# tmod-base.net
KiCad netlist of a schematic drawn in EAGLE
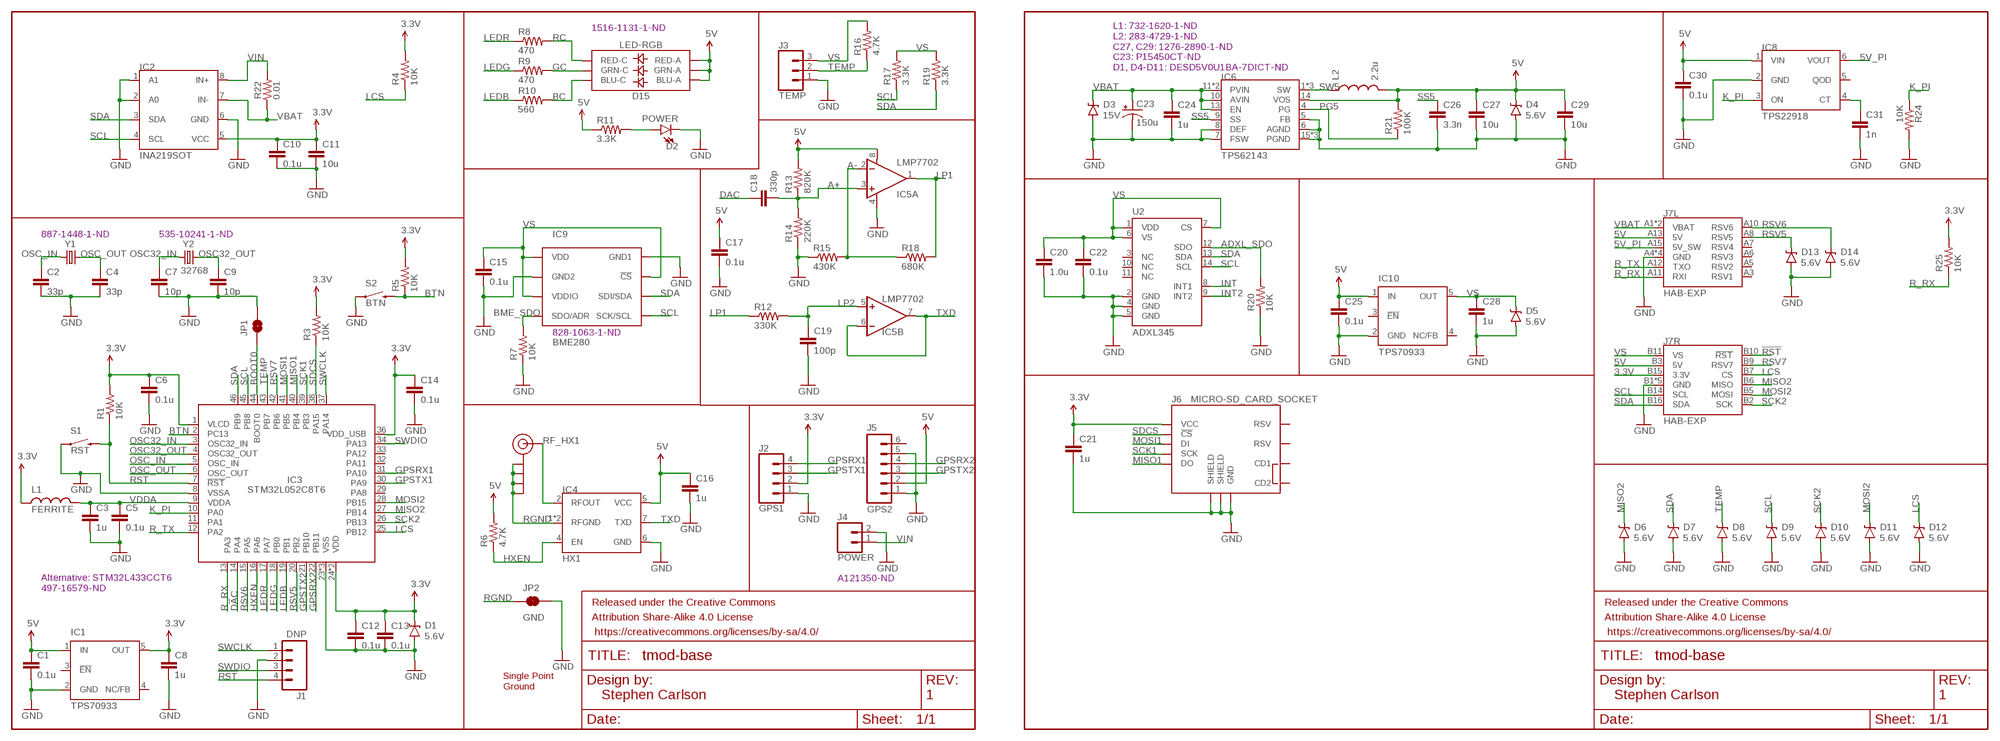
[diagram p0: schematic, sheet 1]

(export (version "E")
  (design (tool "Eeschema 10.0.6"))
  (components
    (comp (ref "C1")
      (value "0.1u")
      (footprint "eagle-import:0805")
      (libsource (lib "eagle-import") (part "CAP0805"))
    )
    (comp (ref "C2")
      (value "33p")
      (footprint "eagle-import:0805")
      (libsource (lib "eagle-import") (part "CAP0805"))
    )
    (comp (ref "C3")
      (value "1u")
      (footprint "eagle-import:0805")
      (libsource (lib "eagle-import") (part "CAP0805"))
    )
    (comp (ref "C4")
      (value "33p")
      (footprint "eagle-import:0805")
      (libsource (lib "eagle-import") (part "CAP0805"))
    )
    (comp (ref "C5")
      (value "0.1u")
      (footprint "eagle-import:0805")
      (libsource (lib "eagle-import") (part "CAP0805"))
    )
    (comp (ref "C6")
      (value "0.1u")
      (footprint "eagle-import:0805")
      (libsource (lib "eagle-import") (part "CAP0805"))
    )
    (comp (ref "C7")
      (value "10p")
      (footprint "eagle-import:0805")
      (libsource (lib "eagle-import") (part "CAP0805"))
    )
    (comp (ref "C8")
      (value "1u")
      (footprint "eagle-import:0805")
      (libsource (lib "eagle-import") (part "CAP0805"))
    )
    (comp (ref "C9")
      (value "10p")
      (footprint "eagle-import:0805")
      (libsource (lib "eagle-import") (part "CAP0805"))
    )
    (comp (ref "C10")
      (value "0.1u")
      (footprint "eagle-import:0805")
      (libsource (lib "eagle-import") (part "CAP0805"))
    )
    (comp (ref "C11")
      (value "10u")
      (footprint "eagle-import:0805")
      (libsource (lib "eagle-import") (part "CAP0805"))
    )
    (comp (ref "C12")
      (value "0.1u")
      (footprint "eagle-import:0805")
      (libsource (lib "eagle-import") (part "CAP0805"))
    )
    (comp (ref "C13")
      (value "0.1u")
      (footprint "eagle-import:0805")
      (libsource (lib "eagle-import") (part "CAP0805"))
    )
    (comp (ref "C14")
      (value "0.1u")
      (footprint "eagle-import:0805")
      (libsource (lib "eagle-import") (part "CAP0805"))
    )
    (comp (ref "C15")
      (value "0.1u")
      (footprint "eagle-import:0805")
      (libsource (lib "eagle-import") (part "CAP0805"))
    )
    (comp (ref "C16")
      (value "1u")
      (footprint "eagle-import:0805")
      (libsource (lib "eagle-import") (part "CAP0805"))
    )
    (comp (ref "C17")
      (value "0.1u")
      (footprint "eagle-import:0805")
      (libsource (lib "eagle-import") (part "CAP0805"))
    )
    (comp (ref "C18")
      (value "330p")
      (footprint "eagle-import:0805")
      (libsource (lib "eagle-import") (part "CAP0805"))
    )
    (comp (ref "C19")
      (value "100p")
      (footprint "eagle-import:0805")
      (libsource (lib "eagle-import") (part "CAP0805"))
    )
    (comp (ref "C20")
      (value "1.0u")
      (footprint "eagle-import:0805")
      (libsource (lib "eagle-import") (part "CAP0805"))
    )
    (comp (ref "C21")
      (value "1u")
      (footprint "eagle-import:0805")
      (libsource (lib "eagle-import") (part "CAP0805"))
    )
    (comp (ref "C22")
      (value "0.1u")
      (footprint "eagle-import:0805")
      (libsource (lib "eagle-import") (part "CAP0805"))
    )
    (comp (ref "C23")
      (value "150u")
      (footprint "eagle-import:PANASONIC_E")
      (libsource (lib "eagle-import") (part "CAP_POLE"))
    )
    (comp (ref "C24")
      (value "1u")
      (footprint "eagle-import:0805")
      (libsource (lib "eagle-import") (part "CAP0805"))
    )
    (comp (ref "C25")
      (value "0.1u")
      (footprint "eagle-import:0805")
      (libsource (lib "eagle-import") (part "CAP0805"))
    )
    (comp (ref "C26")
      (value "3.3n")
      (footprint "eagle-import:0805")
      (libsource (lib "eagle-import") (part "CAP0805"))
    )
    (comp (ref "C27")
      (value "10u")
      (footprint "eagle-import:0805")
      (libsource (lib "eagle-import") (part "CAP0805"))
    )
    (comp (ref "C28")
      (value "1u")
      (footprint "eagle-import:0805")
      (libsource (lib "eagle-import") (part "CAP0805"))
    )
    (comp (ref "C29")
      (value "10u")
      (footprint "eagle-import:0805")
      (libsource (lib "eagle-import") (part "CAP0805"))
    )
    (comp (ref "C30")
      (value "0.1u")
      (footprint "eagle-import:0805")
      (libsource (lib "eagle-import") (part "CAP0805"))
    )
    (comp (ref "C31")
      (value "1n")
      (footprint "eagle-import:0805")
      (libsource (lib "eagle-import") (part "CAP0805"))
    )
    (comp (ref "D1")
      (value "5.6V")
      (footprint "eagle-import:SOD-323")
      (libsource (lib "eagle-import") (part "DIODE-ZENER5.6V"))
    )
    (comp (ref "D2")
      (value "POWER")
      (footprint "eagle-import:LED-0603")
      (libsource (lib "eagle-import") (part "LED-GREEN0603"))
    )
    (comp (ref "D3")
      (value "15V")
      (footprint "eagle-import:SOD-323")
      (libsource (lib "eagle-import") (part "DIODE-ZENER5.6V"))
    )
    (comp (ref "D4")
      (value "5.6V")
      (footprint "eagle-import:SOD-323")
      (libsource (lib "eagle-import") (part "DIODE-ZENER5.6V"))
    )
    (comp (ref "D5")
      (value "5.6V")
      (footprint "eagle-import:SOD-323")
      (libsource (lib "eagle-import") (part "DIODE-ZENER5.6V"))
    )
    (comp (ref "D6")
      (value "5.6V")
      (footprint "eagle-import:SOD-323")
      (libsource (lib "eagle-import") (part "DIODE-ZENER5.6V"))
    )
    (comp (ref "D7")
      (value "5.6V")
      (footprint "eagle-import:SOD-323")
      (libsource (lib "eagle-import") (part "DIODE-ZENER5.6V"))
    )
    (comp (ref "D8")
      (value "5.6V")
      (footprint "eagle-import:SOD-323")
      (libsource (lib "eagle-import") (part "DIODE-ZENER5.6V"))
    )
    (comp (ref "D9")
      (value "5.6V")
      (footprint "eagle-import:SOD-323")
      (libsource (lib "eagle-import") (part "DIODE-ZENER5.6V"))
    )
    (comp (ref "D10")
      (value "5.6V")
      (footprint "eagle-import:SOD-323")
      (libsource (lib "eagle-import") (part "DIODE-ZENER5.6V"))
    )
    (comp (ref "D11")
      (value "5.6V")
      (footprint "eagle-import:SOD-323")
      (libsource (lib "eagle-import") (part "DIODE-ZENER5.6V"))
    )
    (comp (ref "D12")
      (value "5.6V")
      (footprint "eagle-import:SOD-323")
      (libsource (lib "eagle-import") (part "DIODE-ZENER5.6V"))
    )
    (comp (ref "D13")
      (value "5.6V")
      (footprint "eagle-import:SOD-323")
      (libsource (lib "eagle-import") (part "DIODE-ZENER5.6V"))
    )
    (comp (ref "D14")
      (value "5.6V")
      (footprint "eagle-import:SOD-323")
      (libsource (lib "eagle-import") (part "DIODE-ZENER5.6V"))
    )
    (comp (ref "D15")
      (value "LED-RGB")
      (footprint "eagle-import:LED-TRICOLOR-5050")
      (libsource (lib "eagle-import") (part "LED-RGB"))
    )
    (comp (ref "FRAME1")
      (value "FRAME-LETTERNO_PACKAGE")
      (footprint "eagle-import:DUMMY")
      (fields (field (name "DESIGNER") "Nobody"))
      (libsource (lib "eagle-import") (part "FRAME-LETTERNO_PACKAGE"))
    )
    (comp (ref "FRAME2")
      (value "FRAME-LETTERNO_PACKAGE")
      (footprint "eagle-import:DUMMY")
      (fields (field (name "DESIGNER") "Nobody"))
      (libsource (lib "eagle-import") (part "FRAME-LETTERNO_PACKAGE"))
    )
    (comp (ref "IC1")
      (value "TPS70933")
      (footprint "eagle-import:SOT23-DBV")
      (fields (field (name "MF") "TEXAS INSTRUMENTS") (field (name "MPN") "TPS77033DBVT"))
      (libsource (lib "eagle-import") (part "TPS77033"))
    )
    (comp (ref "IC2")
      (value "INA219SOT")
      (footprint "eagle-import:SOT23-8")
      (libsource (lib "eagle-import") (part "INA219SOT"))
    )
    (comp (ref "IC3")
      (value "STM32L052C8T6")
      (footprint "eagle-import:TQFP48")
      (libsource (lib "eagle-import") (part "STM32L07C"))
    )
    (comp (ref "IC4")
      (value "HX1")
      (footprint "eagle-import:HX1")
      (libsource (lib "eagle-import") (part "HX1"))
    )
    (comp (ref "IC5")
      (value "LMP7702")
      (footprint "eagle-import:VSSOP8")
      (libsource (lib "eagle-import") (part "LMP7702VSSOP"))
    )
    (comp (ref "IC6")
      (value "TPS62143")
      (footprint "eagle-import:QFN16-3X3MM")
      (libsource (lib "eagle-import") (part "TPS62140"))
    )
    (comp (ref "IC8")
      (value "TPS22918")
      (footprint "eagle-import:SOT23-6L")
      (libsource (lib "eagle-import") (part "TPS22918"))
    )
    (comp (ref "IC9")
      (value "BME280")
      (footprint "eagle-import:BME280_LGA")
      (libsource (lib "eagle-import") (part "BME280"))
    )
    (comp (ref "IC10")
      (value "TPS70933")
      (footprint "eagle-import:SOT23-DBV")
      (fields (field (name "MF") "TEXAS INSTRUMENTS") (field (name "MPN") "TPS77033DBVT"))
      (libsource (lib "eagle-import") (part "TPS77033"))
    )
    (comp (ref "J$1")
      (value "SMA_EDGE")
      (footprint "eagle-import:SMA-EDGE")
      (libsource (lib "eagle-import") (part "SMA_EDGE"))
    )
    (comp (ref "J1")
      (value "DNP")
      (footprint "eagle-import:1X04_LOCK@1")
      (libsource (lib "eagle-import") (part "M04LOCK"))
    )
    (comp (ref "J2")
      (value "GPS1")
      (footprint "eagle-import:JST-4-PTH")
      (libsource (lib "eagle-import") (part "CONN_04JST-PTH"))
    )
    (comp (ref "J3")
      (value "TEMP")
      (footprint "eagle-import:JST-3-PTH")
      (libsource (lib "eagle-import") (part "CONN_03JST-PTH"))
    )
    (comp (ref "J4")
      (value "POWER")
      (footprint "eagle-import:1X02_SCREW")
      (libsource (lib "eagle-import") (part "1X02"))
    )
    (comp (ref "J5")
      (value "GPS2")
      (footprint "eagle-import:1X06-1MM")
      (libsource (lib "eagle-import") (part "M06SMD-1MM"))
    )
    (comp (ref "J6")
      (value "MICRO-SD_CARD_SOCKET")
      (footprint "eagle-import:MICRO-SD-SOCKET")
      (libsource (lib "eagle-import") (part "MICRO-SD_CARD_SOCKET"))
    )
    (comp (ref "J7")
      (value "HAB-EXP")
      (footprint "eagle-import:HAB-EXP")
      (libsource (lib "eagle-import") (part "HAB-EXP"))
    )
    (comp (ref "JP1")
      (value "JUMPER-SMT_2_NC_TRACE_NO-SILK")
      (footprint "eagle-import:SMT-JUMPER_2_NC_TRACE_NO-SILK")
      (libsource (lib "eagle-import") (part "JUMPER-SMT_2_NC_TRACE_NO-SILK"))
    )
    (comp (ref "JP2")
      (value "GND")
      (footprint "eagle-import:PAD-JUMPER-2-NC_BY_TRACE_YES_SILK")
      (libsource (lib "eagle-import") (part "JUMPER-PAD-2-NC_BY_TRACE"))
    )
    (comp (ref "L1")
      (value "FERRITE")
      (footprint "eagle-import:0805")
      (libsource (lib "eagle-import") (part "INDUCTOR0805"))
    )
    (comp (ref "L2")
      (value "2.2u")
      (footprint "eagle-import:MPIA4012V2")
      (libsource (lib "eagle-import") (part "INDUCTORMPIA4012V2"))
    )
    (comp (ref "R1")
      (value "10K")
      (footprint "eagle-import:0805")
      (libsource (lib "eagle-import") (part "RESISTOR0805-RES"))
    )
    (comp (ref "R3")
      (value "10K")
      (footprint "eagle-import:0805")
      (libsource (lib "eagle-import") (part "RESISTOR0805-RES"))
    )
    (comp (ref "R4")
      (value "10K")
      (footprint "eagle-import:0805")
      (libsource (lib "eagle-import") (part "RESISTOR0805-RES"))
    )
    (comp (ref "R5")
      (value "10K")
      (footprint "eagle-import:0805")
      (libsource (lib "eagle-import") (part "RESISTOR0805-RES"))
    )
    (comp (ref "R6")
      (value "4.7K")
      (footprint "eagle-import:0805")
      (libsource (lib "eagle-import") (part "RESISTOR0805-RES"))
    )
    (comp (ref "R7")
      (value "10K")
      (footprint "eagle-import:0805")
      (libsource (lib "eagle-import") (part "RESISTOR0805-RES"))
    )
    (comp (ref "R8")
      (value "470")
      (footprint "eagle-import:0805")
      (libsource (lib "eagle-import") (part "RESISTOR0805-RES"))
    )
    (comp (ref "R9")
      (value "470")
      (footprint "eagle-import:0805")
      (libsource (lib "eagle-import") (part "RESISTOR0805-RES"))
    )
    (comp (ref "R10")
      (value "560")
      (footprint "eagle-import:0805")
      (libsource (lib "eagle-import") (part "RESISTOR0805-RES"))
    )
    (comp (ref "R11")
      (value "3.3K")
      (footprint "eagle-import:0805")
      (libsource (lib "eagle-import") (part "RESISTOR0805-RES"))
    )
    (comp (ref "R12")
      (value "330K")
      (footprint "eagle-import:0805")
      (libsource (lib "eagle-import") (part "RESISTOR0805-RES"))
    )
    (comp (ref "R13")
      (value "820K")
      (footprint "eagle-import:0805")
      (libsource (lib "eagle-import") (part "RESISTOR0805-RES"))
    )
    (comp (ref "R14")
      (value "220K")
      (footprint "eagle-import:0805")
      (libsource (lib "eagle-import") (part "RESISTOR0805-RES"))
    )
    (comp (ref "R15")
      (value "430K")
      (footprint "eagle-import:0805")
      (libsource (lib "eagle-import") (part "RESISTOR0805-RES"))
    )
    (comp (ref "R16")
      (value "4.7K")
      (footprint "eagle-import:0805")
      (libsource (lib "eagle-import") (part "RESISTOR0805-RES"))
    )
    (comp (ref "R17")
      (value "3.3K")
      (footprint "eagle-import:0805")
      (libsource (lib "eagle-import") (part "RESISTOR0805-RES"))
    )
    (comp (ref "R18")
      (value "680K")
      (footprint "eagle-import:0805")
      (libsource (lib "eagle-import") (part "RESISTOR0805-RES"))
    )
    (comp (ref "R19")
      (value "3.3K")
      (footprint "eagle-import:0805")
      (libsource (lib "eagle-import") (part "RESISTOR0805-RES"))
    )
    (comp (ref "R20")
      (value "10K")
      (footprint "eagle-import:0805")
      (libsource (lib "eagle-import") (part "RESISTOR0805-RES"))
    )
    (comp (ref "R21")
      (value "100K")
      (footprint "eagle-import:0805")
      (libsource (lib "eagle-import") (part "RESISTOR0805-RES"))
    )
    (comp (ref "R22")
      (value "0.01")
      (footprint "eagle-import:1210")
      (libsource (lib "eagle-import") (part "0.1OHM-1210-1/2W-1%"))
    )
    (comp (ref "R24")
      (value "10K")
      (footprint "eagle-import:0805")
      (libsource (lib "eagle-import") (part "RESISTOR0805-RES"))
    )
    (comp (ref "R25")
      (value "10K")
      (footprint "eagle-import:0805")
      (libsource (lib "eagle-import") (part "RESISTOR0805-RES"))
    )
    (comp (ref "S1")
      (value "RST")
      (footprint "eagle-import:TACTILE-PTH-THIN")
      (libsource (lib "eagle-import") (part "SWITCH"))
    )
    (comp (ref "S2")
      (value "BTN")
      (footprint "eagle-import:TACTILE-PTH-THIN")
      (libsource (lib "eagle-import") (part "SWITCH"))
    )
    (comp (ref "U2")
      (value "ADXL345")
      (footprint "eagle-import:LGA14")
      (libsource (lib "eagle-import") (part "ADXL345"))
    )
    (comp (ref "Y1")
      (value "8M")
      (footprint "eagle-import:CRYSTAL-TXC-7A")
      (libsource (lib "eagle-import") (part "CRYSTALTXC-7A"))
    )
    (comp (ref "Y2")
      (value "32768")
      (footprint "eagle-import:ABS25")
      (libsource (lib "eagle-import") (part "CRYSTAL"))
    )
  )
  (nets
    (net (code "1") (name "/5V_PI") (class "Default")
      (node (ref "IC8") (pin "6") (pinfunction "VOUT_6") (pintype "power_in"))
      (node (ref "J7") (pin "A15") (pinfunction "5V_SW_A15") (pintype "power_in"))
    )
    (net (code "2") (name "/A+") (class "Default")
      (node (ref "C18") (pin "2") (pinfunction "2_2") (pintype "passive"))
      (node (ref "IC5") (pin "3") (pinfunction "+IN_3") (pintype "input"))
      (node (ref "R13") (pin "1") (pinfunction "1_1") (pintype "passive"))
      (node (ref "R14") (pin "2") (pinfunction "2_2") (pintype "passive"))
    )
    (net (code "3") (name "/A-") (class "Default")
      (node (ref "IC5") (pin "2") (pinfunction "-IN_2") (pintype "input"))
      (node (ref "R15") (pin "2") (pinfunction "2_2") (pintype "passive"))
      (node (ref "R18") (pin "1") (pinfunction "1_1") (pintype "passive"))
    )
    (net (code "4") (name "/ADXL_SDO") (class "Default")
      (node (ref "R20") (pin "2") (pinfunction "2_2") (pintype "passive"))
      (node (ref "U2") (pin "12") (pinfunction "SDO_12") (pintype "bidirectional"))
    )
    (net (code "5") (name "/BC") (class "Default")
      (node (ref "D15") (pin "1") (pinfunction "BLU-C_1") (pintype "bidirectional"))
      (node (ref "R10") (pin "2") (pinfunction "2_2") (pintype "passive"))
    )
    (net (code "6") (name "/BME_SDO") (class "Default")
      (node (ref "IC9") (pin "P$5") (pinfunction "SDO/ADR_P$5") (pintype "bidirectional"))
      (node (ref "R7") (pin "2") (pinfunction "2_2") (pintype "passive"))
    )
    (net (code "7") (name "/BOOT0") (class "Default")
      (node (ref "IC3") (pin "44") (pinfunction "BOOT0_44") (pintype "input"))
      (node (ref "JP1") (pin "1") (pinfunction "1_1") (pintype "passive"))
    )
    (net (code "8") (name "/BTN") (class "Default")
      (node (ref "IC3") (pin "2") (pinfunction "PC13_2") (pintype "bidirectional"))
      (node (ref "R5") (pin "1") (pinfunction "1_1") (pintype "passive"))
      (node (ref "S2") (pin "2") (pinfunction "2_2") (pintype "passive"))
    )
    (net (code "9") (name "/DAC") (class "Default")
      (node (ref "C18") (pin "1") (pinfunction "1_1") (pintype "passive"))
      (node (ref "IC3") (pin "14") (pinfunction "PA4_14") (pintype "bidirectional"))
    )
    (net (code "10") (name "/GC") (class "Default")
      (node (ref "D15") (pin "2") (pinfunction "GRN-C_2") (pintype "bidirectional"))
      (node (ref "R9") (pin "2") (pinfunction "2_2") (pintype "passive"))
    )
    (net (code "11") (name "/GPSRX1") (class "Default")
      (node (ref "IC3") (pin "31") (pinfunction "PA10_31") (pintype "bidirectional"))
      (node (ref "J2") (pin "4") (pinfunction "4_4") (pintype "passive"))
    )
    (net (code "12") (name "/GPSRX2") (class "Default")
      (node (ref "IC3") (pin "22") (pinfunction "PB11_22") (pintype "bidirectional"))
      (node (ref "J5") (pin "4") (pinfunction "4_4") (pintype "passive"))
    )
    (net (code "13") (name "/GPSTX1") (class "Default")
      (node (ref "IC3") (pin "30") (pinfunction "PA9_30") (pintype "bidirectional"))
      (node (ref "J2") (pin "3") (pinfunction "3_3") (pintype "passive"))
    )
    (net (code "14") (name "/GPSTX2") (class "Default")
      (node (ref "IC3") (pin "21") (pinfunction "PB10_21") (pintype "bidirectional"))
      (node (ref "J5") (pin "3") (pinfunction "3_3") (pintype "passive"))
    )
    (net (code "15") (name "/HXEN") (class "Default")
      (node (ref "IC3") (pin "16") (pinfunction "PA6_16") (pintype "bidirectional"))
      (node (ref "IC4") (pin "4") (pinfunction "EN_4") (pintype "input"))
      (node (ref "R6") (pin "1") (pinfunction "1_1") (pintype "passive"))
    )
    (net (code "16") (name "/INT") (class "Default")
      (node (ref "U2") (pin "8") (pinfunction "INT1_8") (pintype "bidirectional"))
    )
    (net (code "17") (name "/INT2") (class "Default")
      (node (ref "U2") (pin "9") (pinfunction "INT2_9") (pintype "bidirectional"))
    )
    (net (code "18") (name "/K_PI") (class "Default")
      (node (ref "IC3") (pin "10") (pinfunction "PA0_10") (pintype "bidirectional"))
      (node (ref "IC8") (pin "3") (pinfunction "ON_3") (pintype "input"))
      (node (ref "R24") (pin "1") (pinfunction "1_1") (pintype "passive"))
    )
    (net (code "19") (name "/LCS") (class "Default")
      (node (ref "D12") (pin "C") (pinfunction "C_C") (pintype "passive"))
      (node (ref "IC3") (pin "25") (pinfunction "PB12_25") (pintype "bidirectional"))
      (node (ref "J7") (pin "B7") (pinfunction "CS_B7") (pintype "bidirectional"))
      (node (ref "R4") (pin "1") (pinfunction "1_1") (pintype "passive"))
    )
    (net (code "20") (name "/LEDB") (class "Default")
      (node (ref "IC3") (pin "19") (pinfunction "PB1_19") (pintype "bidirectional"))
      (node (ref "R10") (pin "1") (pinfunction "1_1") (pintype "passive"))
    )
    (net (code "21") (name "/LEDG") (class "Default")
      (node (ref "IC3") (pin "18") (pinfunction "PB0_18") (pintype "bidirectional"))
      (node (ref "R9") (pin "1") (pinfunction "1_1") (pintype "passive"))
    )
    (net (code "22") (name "/LEDR") (class "Default")
      (node (ref "IC3") (pin "17") (pinfunction "PA7_17") (pintype "bidirectional"))
      (node (ref "R8") (pin "1") (pinfunction "1_1") (pintype "passive"))
    )
    (net (code "23") (name "/LP1") (class "Default")
      (node (ref "IC5") (pin "1") (pinfunction "OUT_1") (pintype "output"))
      (node (ref "R12") (pin "1") (pinfunction "1_1") (pintype "passive"))
      (node (ref "R18") (pin "2") (pinfunction "2_2") (pintype "passive"))
    )
    (net (code "24") (name "/LP2") (class "Default")
      (node (ref "C19") (pin "1") (pinfunction "1_1") (pintype "passive"))
      (node (ref "IC5") (pin "5") (pinfunction "+IN_5") (pintype "input"))
      (node (ref "R12") (pin "2") (pinfunction "2_2") (pintype "passive"))
    )
    (net (code "25") (name "/MISO1") (class "Default")
      (node (ref "IC3") (pin "40") (pinfunction "PB4_40") (pintype "bidirectional"))
      (node (ref "J6") (pin "DO") (pinfunction "DO_DO") (pintype "bidirectional"))
    )
    (net (code "26") (name "/MISO2") (class "Default")
      (node (ref "D6") (pin "C") (pinfunction "C_C") (pintype "passive"))
      (node (ref "IC3") (pin "27") (pinfunction "PB14_27") (pintype "bidirectional"))
      (node (ref "J7") (pin "B6") (pinfunction "MISO_B6") (pintype "bidirectional"))
    )
    (net (code "27") (name "/MOSI1") (class "Default")
      (node (ref "IC3") (pin "41") (pinfunction "PB5_41") (pintype "bidirectional"))
      (node (ref "J6") (pin "DI") (pinfunction "DI_DI") (pintype "bidirectional"))
    )
    (net (code "28") (name "/MOSI2") (class "Default")
      (node (ref "D11") (pin "C") (pinfunction "C_C") (pintype "passive"))
      (node (ref "IC3") (pin "28") (pinfunction "PB15_28") (pintype "bidirectional"))
      (node (ref "J7") (pin "B5") (pinfunction "MOSI_B5") (pintype "bidirectional"))
    )
    (net (code "29") (name "/OSC32_IN") (class "Default")
      (node (ref "C7") (pin "1") (pinfunction "1_1") (pintype "passive"))
      (node (ref "IC3") (pin "3") (pinfunction "OSC32_IN_3") (pintype "bidirectional"))
      (node (ref "Y2") (pin "1") (pinfunction "1_1") (pintype "passive"))
    )
    (net (code "30") (name "/OSC32_OUT") (class "Default")
      (node (ref "C9") (pin "1") (pinfunction "1_1") (pintype "passive"))
      (node (ref "IC3") (pin "4") (pinfunction "OSC32_OUT_4") (pintype "bidirectional"))
      (node (ref "Y2") (pin "4") (pinfunction "2_4") (pintype "passive"))
    )
    (net (code "31") (name "/OSC_IN") (class "Default")
      (node (ref "C2") (pin "1") (pinfunction "1_1") (pintype "passive"))
      (node (ref "IC3") (pin "5") (pinfunction "OSC_IN_5") (pintype "bidirectional"))
      (node (ref "Y1") (pin "P$1") (pinfunction "1_P$1") (pintype "passive"))
    )
    (net (code "32") (name "/OSC_OUT") (class "Default")
      (node (ref "C4") (pin "1") (pinfunction "1_1") (pintype "passive"))
      (node (ref "IC3") (pin "6") (pinfunction "OSC_OUT_6") (pintype "bidirectional"))
      (node (ref "Y1") (pin "P$2") (pinfunction "2_P$2") (pintype "passive"))
    )
    (net (code "33") (name "/PG5") (class "Default")
      (node (ref "IC6") (pin "4") (pinfunction "PG_4") (pintype "open_collector"))
      (node (ref "R21") (pin "1") (pinfunction "1_1") (pintype "passive"))
    )
    (net (code "34") (name "/RC") (class "Default")
      (node (ref "D15") (pin "3") (pinfunction "RED-C_3") (pintype "bidirectional"))
      (node (ref "R8") (pin "2") (pinfunction "2_2") (pintype "passive"))
    )
    (net (code "35") (name "/RF_HX1") (class "Default")
      (node (ref "IC4") (pin "2") (pinfunction "RFOUT_2") (pintype "output"))
      (node (ref "J$1") (pin "SIG") (pinfunction "SIGNAL_SIG") (pintype "bidirectional"))
    )
    (net (code "36") (name "/RGND") (class "Default")
      (node (ref "IC4") (pin "1") (pinfunction "RFGND_1") (pintype "power_in"))
      (node (ref "IC4") (pin "3") (pinfunction "RFGND_3") (pintype "power_in"))
      (node (ref "J$1") (pin "GND@0") (pinfunction "GND_GND@0") (pintype "bidirectional"))
      (node (ref "J$1") (pin "GND@1") (pinfunction "GND_GND@1") (pintype "bidirectional"))
      (node (ref "J$1") (pin "GND@2") (pinfunction "GND_GND@2") (pintype "bidirectional"))
      (node (ref "J$1") (pin "GND@3") (pinfunction "GND_GND@3") (pintype "bidirectional"))
      (node (ref "JP2") (pin "1") (pinfunction "1_1") (pintype "passive"))
    )
    (net (code "37") (name "/RSV5") (class "Default")
      (node (ref "D13") (pin "C") (pinfunction "C_C") (pintype "passive"))
      (node (ref "IC3") (pin "20") (pinfunction "PB2_20") (pintype "bidirectional"))
      (node (ref "J7") (pin "A8") (pinfunction "RSV5_A8") (pintype "bidirectional"))
    )
    (net (code "38") (name "/RSV6") (class "Default")
      (node (ref "D14") (pin "C") (pinfunction "C_C") (pintype "passive"))
      (node (ref "IC3") (pin "15") (pinfunction "PA5_15") (pintype "bidirectional"))
      (node (ref "J7") (pin "A10") (pinfunction "RSV6_A10") (pintype "bidirectional"))
    )
    (net (code "39") (name "/RSV7") (class "Default")
      (node (ref "IC3") (pin "42") (pinfunction "PB6_42") (pintype "bidirectional"))
      (node (ref "J7") (pin "B9") (pinfunction "RSV7_B9") (pintype "bidirectional"))
    )
    (net (code "40") (name "/R_RX") (class "Default")
      (node (ref "IC3") (pin "13") (pinfunction "PA3_13") (pintype "bidirectional"))
      (node (ref "J7") (pin "A11") (pinfunction "RXI_A11") (pintype "input"))
      (node (ref "R25") (pin "1") (pinfunction "1_1") (pintype "passive"))
    )
    (net (code "41") (name "/R_TX") (class "Default")
      (node (ref "IC3") (pin "12") (pinfunction "PA2_12") (pintype "bidirectional"))
      (node (ref "J7") (pin "A12") (pinfunction "TXO_A12") (pintype "output"))
    )
    (net (code "42") (name "/SCK1") (class "Default")
      (node (ref "IC3") (pin "39") (pinfunction "PB3_39") (pintype "bidirectional"))
      (node (ref "J6") (pin "SCLK") (pinfunction "SCK_SCLK") (pintype "bidirectional"))
    )
    (net (code "43") (name "/SCK2") (class "Default")
      (node (ref "D10") (pin "C") (pinfunction "C_C") (pintype "passive"))
      (node (ref "IC3") (pin "26") (pinfunction "PB13_26") (pintype "bidirectional"))
      (node (ref "J7") (pin "B2") (pinfunction "SCK_B2") (pintype "bidirectional"))
    )
    (net (code "44") (name "/SCL") (class "Default")
      (node (ref "D9") (pin "C") (pinfunction "C_C") (pintype "passive"))
      (node (ref "IC2") (pin "4") (pinfunction "SCL_4") (pintype "bidirectional"))
      (node (ref "IC3") (pin "45") (pinfunction "PB8_45") (pintype "bidirectional"))
      (node (ref "IC9") (pin "P$4") (pinfunction "SCK/SCL_P$4") (pintype "bidirectional"))
      (node (ref "J7") (pin "B14") (pinfunction "SCL_B14") (pintype "bidirectional"))
      (node (ref "R17") (pin "1") (pinfunction "1_1") (pintype "passive"))
      (node (ref "U2") (pin "14") (pinfunction "SCL_14") (pintype "bidirectional"))
    )
    (net (code "45") (name "/SDA") (class "Default")
      (node (ref "D7") (pin "C") (pinfunction "C_C") (pintype "passive"))
      (node (ref "IC2") (pin "3") (pinfunction "SDA_3") (pintype "bidirectional"))
      (node (ref "IC3") (pin "46") (pinfunction "PB9_46") (pintype "bidirectional"))
      (node (ref "IC9") (pin "P$3") (pinfunction "SDI/SDA_P$3") (pintype "bidirectional"))
      (node (ref "J7") (pin "B16") (pinfunction "SDA_B16") (pintype "bidirectional"))
      (node (ref "R19") (pin "1") (pinfunction "1_1") (pintype "passive"))
      (node (ref "U2") (pin "13") (pinfunction "SDA_13") (pintype "bidirectional"))
    )
    (net (code "46") (name "/SDCS") (class "Default")
      (node (ref "IC3") (pin "38") (pinfunction "PA15_38") (pintype "bidirectional"))
      (node (ref "J6") (pin "CS") (pinfunction "~{CS}_CS") (pintype "bidirectional"))
      (node (ref "R3") (pin "1") (pinfunction "1_1") (pintype "passive"))
    )
    (net (code "47") (name "/SS5") (class "Default")
      (node (ref "C26") (pin "1") (pinfunction "1_1") (pintype "passive"))
      (node (ref "IC6") (pin "9") (pinfunction "SS_9") (pintype "passive"))
    )
    (net (code "48") (name "/SW5") (class "Default")
      (node (ref "IC6") (pin "1") (pinfunction "SW_1") (pintype "power_in"))
      (node (ref "IC6") (pin "2") (pinfunction "SW_2") (pintype "power_in"))
      (node (ref "IC6") (pin "3") (pinfunction "SW_3") (pintype "power_in"))
      (node (ref "L2") (pin "1") (pinfunction "1_1") (pintype "passive"))
    )
    (net (code "49") (name "/SWCLK") (class "Default")
      (node (ref "IC3") (pin "37") (pinfunction "PA14_37") (pintype "bidirectional"))
      (node (ref "J1") (pin "1") (pinfunction "1_1") (pintype "passive"))
    )
    (net (code "50") (name "/SWDIO") (class "Default")
      (node (ref "IC3") (pin "34") (pinfunction "PA13_34") (pintype "bidirectional"))
      (node (ref "J1") (pin "3") (pinfunction "3_3") (pintype "passive"))
    )
    (net (code "51") (name "/TEMP") (class "Default")
      (node (ref "D8") (pin "C") (pinfunction "C_C") (pintype "passive"))
      (node (ref "IC3") (pin "43") (pinfunction "PB7_43") (pintype "bidirectional"))
      (node (ref "J3") (pin "2") (pinfunction "2_2") (pintype "passive"))
      (node (ref "R16") (pin "1") (pinfunction "1_1") (pintype "passive"))
    )
    (net (code "52") (name "/TXD") (class "Default")
      (node (ref "IC4") (pin "7") (pinfunction "TXD_7") (pintype "input"))
      (node (ref "IC5") (pin "6") (pinfunction "-IN_6") (pintype "input"))
      (node (ref "IC5") (pin "7") (pinfunction "OUT_7") (pintype "output"))
    )
    (net (code "53") (name "/VBAT") (class "Default")
      (node (ref "C23") (pin "+") (pinfunction "+_+") (pintype "passive"))
      (node (ref "C24") (pin "1") (pinfunction "1_1") (pintype "passive"))
      (node (ref "D3") (pin "C") (pinfunction "C_C") (pintype "passive"))
      (node (ref "IC2") (pin "7") (pinfunction "IN-_7") (pintype "passive"))
      (node (ref "IC6") (pin "10") (pinfunction "AVIN_10") (pintype "power_in"))
      (node (ref "IC6") (pin "11") (pinfunction "PVIN_11") (pintype "power_in"))
      (node (ref "IC6") (pin "12") (pinfunction "PVIN_12") (pintype "power_in"))
      (node (ref "IC6") (pin "13") (pinfunction "EN_13") (pintype "input"))
      (node (ref "J7") (pin "A1") (pinfunction "VBAT_A1") (pintype "power_in"))
      (node (ref "J7") (pin "A2") (pinfunction "VBAT_A2") (pintype "power_in"))
      (node (ref "R22") (pin "1") (pinfunction "1_1") (pintype "passive"))
    )
    (net (code "54") (name "/VDDA") (class "Default")
      (node (ref "C3") (pin "1") (pinfunction "1_1") (pintype "passive"))
      (node (ref "C5") (pin "1") (pinfunction "1_1") (pintype "passive"))
      (node (ref "IC3") (pin "9") (pinfunction "VDDA_9") (pintype "power_in"))
      (node (ref "L1") (pin "2") (pinfunction "2_2") (pintype "passive"))
    )
    (net (code "55") (name "/VIN") (class "Default")
      (node (ref "IC2") (pin "8") (pinfunction "IN+_8") (pintype "passive"))
      (node (ref "J4") (pin "1") (pinfunction "1_1") (pintype "passive"))
      (node (ref "R22") (pin "2") (pinfunction "2_2") (pintype "passive"))
    )
    (net (code "56") (name "/VS") (class "Default")
      (node (ref "C15") (pin "1") (pinfunction "1_1") (pintype "passive"))
      (node (ref "C20") (pin "1") (pinfunction "1_1") (pintype "passive"))
      (node (ref "C22") (pin "1") (pinfunction "1_1") (pintype "passive"))
      (node (ref "C28") (pin "1") (pinfunction "1_1") (pintype "passive"))
      (node (ref "D5") (pin "C") (pinfunction "C_C") (pintype "passive"))
      (node (ref "IC10") (pin "5") (pinfunction "OUT_5") (pintype "passive"))
      (node (ref "IC9") (pin "P$2") (pinfunction "~{CS}_P$2") (pintype "bidirectional"))
      (node (ref "IC9") (pin "P$6") (pinfunction "VDDIO_P$6") (pintype "bidirectional"))
      (node (ref "IC9") (pin "P$8") (pinfunction "VDD_P$8") (pintype "bidirectional"))
      (node (ref "J3") (pin "3") (pinfunction "3_3") (pintype "passive"))
      (node (ref "J7") (pin "B11") (pinfunction "VS_B11") (pintype "power_in"))
      (node (ref "R16") (pin "2") (pinfunction "2_2") (pintype "passive"))
      (node (ref "R17") (pin "2") (pinfunction "2_2") (pintype "passive"))
      (node (ref "R19") (pin "2") (pinfunction "2_2") (pintype "passive"))
      (node (ref "U2") (pin "1") (pinfunction "VDD_1") (pintype "bidirectional"))
      (node (ref "U2") (pin "6") (pinfunction "VS_6") (pintype "bidirectional"))
      (node (ref "U2") (pin "7") (pinfunction "CS_7") (pintype "bidirectional"))
    )
    (net (code "57") (name "/~{RST}") (class "Default")
      (node (ref "IC3") (pin "7") (pinfunction "~{RST}_7") (pintype "input"))
      (node (ref "J1") (pin "4") (pinfunction "4_4") (pintype "passive"))
      (node (ref "J7") (pin "B10") (pinfunction "~{RST}_B10") (pintype "bidirectional"))
      (node (ref "R1") (pin "1") (pinfunction "1_1") (pintype "passive"))
      (node (ref "S1") (pin "2") (pinfunction "2_2") (pintype "passive"))
    )
    (net (code "58") (name "3.3V") (class "Default")
      (node (ref "C10") (pin "1") (pinfunction "1_1") (pintype "passive"))
      (node (ref "C11") (pin "1") (pinfunction "1_1") (pintype "passive"))
      (node (ref "C12") (pin "1") (pinfunction "1_1") (pintype "passive"))
      (node (ref "C13") (pin "1") (pinfunction "1_1") (pintype "passive"))
      (node (ref "C14") (pin "1") (pinfunction "1_1") (pintype "passive"))
      (node (ref "C21") (pin "1") (pinfunction "1_1") (pintype "passive"))
      (node (ref "C6") (pin "1") (pinfunction "1_1") (pintype "passive"))
      (node (ref "C8") (pin "1") (pinfunction "1_1") (pintype "passive"))
      (node (ref "D1") (pin "C") (pinfunction "C_C") (pintype "passive"))
      (node (ref "IC1") (pin "5") (pinfunction "OUT_5") (pintype "passive"))
      (node (ref "IC2") (pin "5") (pinfunction "VCC_5") (pintype "power_in"))
      (node (ref "IC3") (pin "1") (pinfunction "VLCD_1") (pintype "power_in"))
      (node (ref "IC3") (pin "24") (pinfunction "VDD_24") (pintype "power_in"))
      (node (ref "IC3") (pin "36") (pinfunction "VDD_USB_36") (pintype "power_in"))
      (node (ref "IC3") (pin "48") (pinfunction "VDD_48") (pintype "power_in"))
      (node (ref "J2") (pin "2") (pinfunction "2_2") (pintype "passive"))
      (node (ref "J6") (pin "VCC") (pinfunction "VCC_VCC") (pintype "bidirectional"))
      (node (ref "J7") (pin "B15") (pinfunction "3.3V_B15") (pintype "power_in"))
      (node (ref "L1") (pin "1") (pinfunction "1_1") (pintype "passive"))
      (node (ref "R1") (pin "2") (pinfunction "2_2") (pintype "passive"))
      (node (ref "R25") (pin "2") (pinfunction "2_2") (pintype "passive"))
      (node (ref "R3") (pin "2") (pinfunction "2_2") (pintype "passive"))
      (node (ref "R4") (pin "2") (pinfunction "2_2") (pintype "passive"))
      (node (ref "R5") (pin "2") (pinfunction "2_2") (pintype "passive"))
    )
    (net (code "59") (name "5V") (class "Default")
      (node (ref "C1") (pin "1") (pinfunction "1_1") (pintype "passive"))
      (node (ref "C16") (pin "1") (pinfunction "1_1") (pintype "passive"))
      (node (ref "C17") (pin "1") (pinfunction "1_1") (pintype "passive"))
      (node (ref "C25") (pin "1") (pinfunction "1_1") (pintype "passive"))
      (node (ref "C27") (pin "1") (pinfunction "1_1") (pintype "passive"))
      (node (ref "C29") (pin "1") (pinfunction "1_1") (pintype "passive"))
      (node (ref "C30") (pin "1") (pinfunction "1_1") (pintype "passive"))
      (node (ref "D15") (pin "4") (pinfunction "RED-A_4") (pintype "bidirectional"))
      (node (ref "D15") (pin "5") (pinfunction "GRN-A_5") (pintype "bidirectional"))
      (node (ref "D15") (pin "6") (pinfunction "BLU-A_6") (pintype "bidirectional"))
      (node (ref "D4") (pin "C") (pinfunction "C_C") (pintype "passive"))
      (node (ref "IC1") (pin "1") (pinfunction "IN_1") (pintype "input"))
      (node (ref "IC10") (pin "1") (pinfunction "IN_1") (pintype "input"))
      (node (ref "IC4") (pin "5") (pinfunction "VCC_5") (pintype "power_in"))
      (node (ref "IC5") (pin "8") (pinfunction "V+_8") (pintype "power_in"))
      (node (ref "IC6") (pin "14") (pinfunction "VOS_14") (pintype "input"))
      (node (ref "IC8") (pin "1") (pinfunction "VIN_1") (pintype "power_in"))
      (node (ref "J5") (pin "2") (pinfunction "2_2") (pintype "passive"))
      (node (ref "J7") (pin "A13") (pinfunction "5V_A13") (pintype "power_in"))
      (node (ref "J7") (pin "B3") (pinfunction "5V_B3") (pintype "power_in"))
      (node (ref "L2") (pin "2") (pinfunction "2_2") (pintype "passive"))
      (node (ref "R11") (pin "1") (pinfunction "1_1") (pintype "passive"))
      (node (ref "R13") (pin "2") (pinfunction "2_2") (pintype "passive"))
      (node (ref "R21") (pin "2") (pinfunction "2_2") (pintype "passive"))
      (node (ref "R6") (pin "2") (pinfunction "2_2") (pintype "passive"))
    )
    (net (code "60") (name "GND") (class "Default")
      (node (ref "C1") (pin "2") (pinfunction "2_2") (pintype "passive"))
      (node (ref "C10") (pin "2") (pinfunction "2_2") (pintype "passive"))
      (node (ref "C11") (pin "2") (pinfunction "2_2") (pintype "passive"))
      (node (ref "C12") (pin "2") (pinfunction "2_2") (pintype "passive"))
      (node (ref "C13") (pin "2") (pinfunction "2_2") (pintype "passive"))
      (node (ref "C14") (pin "2") (pinfunction "2_2") (pintype "passive"))
      (node (ref "C15") (pin "2") (pinfunction "2_2") (pintype "passive"))
      (node (ref "C16") (pin "2") (pinfunction "2_2") (pintype "passive"))
      (node (ref "C17") (pin "2") (pinfunction "2_2") (pintype "passive"))
      (node (ref "C19") (pin "2") (pinfunction "2_2") (pintype "passive"))
      (node (ref "C2") (pin "2") (pinfunction "2_2") (pintype "passive"))
      (node (ref "C20") (pin "2") (pinfunction "2_2") (pintype "passive"))
      (node (ref "C21") (pin "2") (pinfunction "2_2") (pintype "passive"))
      (node (ref "C22") (pin "2") (pinfunction "2_2") (pintype "passive"))
      (node (ref "C23") (pin "-") (pinfunction "-_-") (pintype "passive"))
      (node (ref "C24") (pin "2") (pinfunction "2_2") (pintype "passive"))
      (node (ref "C25") (pin "2") (pinfunction "2_2") (pintype "passive"))
      (node (ref "C26") (pin "2") (pinfunction "2_2") (pintype "passive"))
      (node (ref "C27") (pin "2") (pinfunction "2_2") (pintype "passive"))
      (node (ref "C28") (pin "2") (pinfunction "2_2") (pintype "passive"))
      (node (ref "C29") (pin "2") (pinfunction "2_2") (pintype "passive"))
      (node (ref "C3") (pin "2") (pinfunction "2_2") (pintype "passive"))
      (node (ref "C30") (pin "2") (pinfunction "2_2") (pintype "passive"))
      (node (ref "C31") (pin "2") (pinfunction "2_2") (pintype "passive"))
      (node (ref "C4") (pin "2") (pinfunction "2_2") (pintype "passive"))
      (node (ref "C5") (pin "2") (pinfunction "2_2") (pintype "passive"))
      (node (ref "C6") (pin "2") (pinfunction "2_2") (pintype "passive"))
      (node (ref "C7") (pin "2") (pinfunction "2_2") (pintype "passive"))
      (node (ref "C8") (pin "2") (pinfunction "2_2") (pintype "passive"))
      (node (ref "C9") (pin "2") (pinfunction "2_2") (pintype "passive"))
      (node (ref "D1") (pin "A") (pinfunction "A_A") (pintype "passive"))
      (node (ref "D10") (pin "A") (pinfunction "A_A") (pintype "passive"))
      (node (ref "D11") (pin "A") (pinfunction "A_A") (pintype "passive"))
      (node (ref "D12") (pin "A") (pinfunction "A_A") (pintype "passive"))
      (node (ref "D13") (pin "A") (pinfunction "A_A") (pintype "passive"))
      (node (ref "D14") (pin "A") (pinfunction "A_A") (pintype "passive"))
      (node (ref "D2") (pin "C") (pinfunction "C_C") (pintype "passive"))
      (node (ref "D3") (pin "A") (pinfunction "A_A") (pintype "passive"))
      (node (ref "D4") (pin "A") (pinfunction "A_A") (pintype "passive"))
      (node (ref "D5") (pin "A") (pinfunction "A_A") (pintype "passive"))
      (node (ref "D6") (pin "A") (pinfunction "A_A") (pintype "passive"))
      (node (ref "D7") (pin "A") (pinfunction "A_A") (pintype "passive"))
      (node (ref "D8") (pin "A") (pinfunction "A_A") (pintype "passive"))
      (node (ref "D9") (pin "A") (pinfunction "A_A") (pintype "passive"))
      (node (ref "IC1") (pin "2") (pinfunction "GND_2") (pintype "power_in"))
      (node (ref "IC10") (pin "2") (pinfunction "GND_2") (pintype "power_in"))
      (node (ref "IC2") (pin "1") (pinfunction "A1_1") (pintype "input"))
      (node (ref "IC2") (pin "2") (pinfunction "A0_2") (pintype "input"))
      (node (ref "IC2") (pin "6") (pinfunction "GND_6") (pintype "power_in"))
      (node (ref "IC3") (pin "23") (pinfunction "VSS_23") (pintype "power_in"))
      (node (ref "IC3") (pin "35") (pinfunction "VSS_35") (pintype "power_in"))
      (node (ref "IC3") (pin "47") (pinfunction "VSS_47") (pintype "power_in"))
      (node (ref "IC3") (pin "8") (pinfunction "VSSA_8") (pintype "power_in"))
      (node (ref "IC4") (pin "6") (pinfunction "GND_6") (pintype "power_in"))
      (node (ref "IC5") (pin "4") (pinfunction "V-_4") (pintype "power_in"))
      (node (ref "IC6") (pin "15") (pinfunction "PGND_15") (pintype "power_in"))
      (node (ref "IC6") (pin "16") (pinfunction "PGND_16") (pintype "power_in"))
      (node (ref "IC6") (pin "5") (pinfunction "FB_5") (pintype "input"))
      (node (ref "IC6") (pin "6") (pinfunction "AGND_6") (pintype "power_in"))
      (node (ref "IC6") (pin "7") (pinfunction "FSW_7") (pintype "input"))
      (node (ref "IC6") (pin "8") (pinfunction "DEF_8") (pintype "input"))
      (node (ref "IC6") (pin "EXT") (pinfunction "PGND_EXT") (pintype "power_in"))
      (node (ref "IC8") (pin "2") (pinfunction "GND_2") (pintype "power_in"))
      (node (ref "IC9") (pin "P$1") (pinfunction "GND1_P$1") (pintype "bidirectional"))
      (node (ref "IC9") (pin "P$7") (pinfunction "GND2_P$7") (pintype "bidirectional"))
      (node (ref "J1") (pin "2") (pinfunction "2_2") (pintype "passive"))
      (node (ref "J2") (pin "1") (pinfunction "1_1") (pintype "passive"))
      (node (ref "J3") (pin "1") (pinfunction "1_1") (pintype "passive"))
      (node (ref "J4") (pin "2") (pinfunction "2_2") (pintype "passive"))
      (node (ref "J5") (pin "1") (pinfunction "1_1") (pintype "passive"))
      (node (ref "J5") (pin "5") (pinfunction "5_5") (pintype "passive"))
      (node (ref "J6") (pin "GND") (pinfunction "GND_GND") (pintype "bidirectional"))
      (node (ref "J6") (pin "GND1") (pinfunction "SHIELD_GND1") (pintype "bidirectional"))
      (node (ref "J6") (pin "GND3") (pinfunction "SHIELD_GND3") (pintype "bidirectional"))
      (node (ref "J7") (pin "A14") (pinfunction "GND_A14") (pintype "power_in"))
      (node (ref "J7") (pin "A16") (pinfunction "GND_A16") (pintype "power_in"))
      (node (ref "J7") (pin "A4") (pinfunction "GND_A4") (pintype "power_in"))
      (node (ref "J7") (pin "A9") (pinfunction "GND_A9") (pintype "power_in"))
      (node (ref "J7") (pin "B1") (pinfunction "GND_B1") (pintype "power_in"))
      (node (ref "J7") (pin "B12") (pinfunction "GND_B12") (pintype "power_in"))
      (node (ref "J7") (pin "B13") (pinfunction "GND_B13") (pintype "power_in"))
      (node (ref "J7") (pin "B4") (pinfunction "GND_B4") (pintype "power_in"))
      (node (ref "J7") (pin "B8") (pinfunction "GND_B8") (pintype "power_in"))
      (node (ref "JP1") (pin "2") (pinfunction "2_2") (pintype "passive"))
      (node (ref "JP2") (pin "2") (pinfunction "2_2") (pintype "passive"))
      (node (ref "R14") (pin "1") (pinfunction "1_1") (pintype "passive"))
      (node (ref "R15") (pin "1") (pinfunction "1_1") (pintype "passive"))
      (node (ref "R20") (pin "1") (pinfunction "1_1") (pintype "passive"))
      (node (ref "R24") (pin "2") (pinfunction "2_2") (pintype "passive"))
      (node (ref "R7") (pin "1") (pinfunction "1_1") (pintype "passive"))
      (node (ref "S1") (pin "1") (pinfunction "1_1") (pintype "passive"))
      (node (ref "S2") (pin "1") (pinfunction "1_1") (pintype "passive"))
      (node (ref "U2") (pin "2") (pinfunction "GND_2") (pintype "bidirectional"))
      (node (ref "U2") (pin "4") (pinfunction "GND_4") (pintype "bidirectional"))
      (node (ref "U2") (pin "5") (pinfunction "GND_5") (pintype "bidirectional"))
    )
    (net (code "61") (name "Net-(D2-PadA)") (class "Default")
      (node (ref "D2") (pin "A") (pinfunction "A_A") (pintype "passive"))
      (node (ref "R11") (pin "2") (pinfunction "2_2") (pintype "passive"))
    )
    (net (code "62") (name "Net-(IC8-CT)") (class "Default")
      (node (ref "C31") (pin "1") (pinfunction "1_1") (pintype "passive"))
      (node (ref "IC8") (pin "4") (pinfunction "CT_4") (pintype "passive"))
    )
    (net (code "63") (name "unconnected-(IC1-NC{slash}FB-Pad4)") (class "Default")
      (node (ref "IC1") (pin "4") (pinfunction "NC/FB_4") (pintype "passive"))
    )
    (net (code "64") (name "unconnected-(IC1-~{EN}-Pad3)") (class "Default")
      (node (ref "IC1") (pin "3") (pinfunction "~{EN}_3") (pintype "input"))
    )
    (net (code "65") (name "unconnected-(IC3-PA1-Pad11)") (class "Default")
      (node (ref "IC3") (pin "11") (pinfunction "PA1_11") (pintype "bidirectional"))
    )
    (net (code "66") (name "unconnected-(IC3-PA8-Pad29)") (class "Default")
      (node (ref "IC3") (pin "29") (pinfunction "PA8_29") (pintype "bidirectional"))
    )
    (net (code "67") (name "unconnected-(IC3-PA11-Pad32)") (class "Default")
      (node (ref "IC3") (pin "32") (pinfunction "PA11_32") (pintype "bidirectional"))
    )
    (net (code "68") (name "unconnected-(IC3-PA12-Pad33)") (class "Default")
      (node (ref "IC3") (pin "33") (pinfunction "PA12_33") (pintype "bidirectional"))
    )
    (net (code "69") (name "unconnected-(IC8-QOD-Pad5)") (class "Default")
      (node (ref "IC8") (pin "5") (pinfunction "QOD_5") (pintype "passive"))
    )
    (net (code "70") (name "unconnected-(IC10-NC{slash}FB-Pad4)") (class "Default")
      (node (ref "IC10") (pin "4") (pinfunction "NC/FB_4") (pintype "passive"))
    )
    (net (code "71") (name "unconnected-(IC10-~{EN}-Pad3)") (class "Default")
      (node (ref "IC10") (pin "3") (pinfunction "~{EN}_3") (pintype "input"))
    )
    (net (code "72") (name "unconnected-(J5-Pad6)") (class "Default")
      (node (ref "J5") (pin "6") (pinfunction "6_6") (pintype "passive"))
    )
    (net (code "73") (name "unconnected-(J6-PadCD1)") (class "Default")
      (node (ref "J6") (pin "CD1") (pinfunction "CD1_CD1") (pintype "bidirectional"))
    )
    (net (code "74") (name "unconnected-(J6-PadCD2)") (class "Default")
      (node (ref "J6") (pin "CD2") (pinfunction "CD2_CD2") (pintype "bidirectional"))
    )
    (net (code "75") (name "unconnected-(J6-RSV-PadRSV1)") (class "Default")
      (node (ref "J6") (pin "RSV1") (pinfunction "RSV_RSV1") (pintype "bidirectional"))
    )
    (net (code "76") (name "unconnected-(J6-RSV-PadRSV2)") (class "Default")
      (node (ref "J6") (pin "RSV2") (pinfunction "RSV_RSV2") (pintype "bidirectional"))
    )
    (net (code "77") (name "unconnected-(J7A-RSV1-PadA3)") (class "Default")
      (node (ref "J7") (pin "A3") (pinfunction "RSV1_A3") (pintype "bidirectional"))
    )
    (net (code "78") (name "unconnected-(J7A-RSV2-PadA5)") (class "Default")
      (node (ref "J7") (pin "A5") (pinfunction "RSV2_A5") (pintype "bidirectional"))
    )
    (net (code "79") (name "unconnected-(J7A-RSV3-PadA6)") (class "Default")
      (node (ref "J7") (pin "A6") (pinfunction "RSV3_A6") (pintype "bidirectional"))
    )
    (net (code "80") (name "unconnected-(J7A-RSV4-PadA7)") (class "Default")
      (node (ref "J7") (pin "A7") (pinfunction "RSV4_A7") (pintype "bidirectional"))
    )
    (net (code "81") (name "unconnected-(U2-NC-Pad3)") (class "Default")
      (node (ref "U2") (pin "3") (pinfunction "NC_3") (pintype "bidirectional"))
    )
    (net (code "82") (name "unconnected-(U2-NC-Pad10)") (class "Default")
      (node (ref "U2") (pin "10") (pinfunction "NC_10") (pintype "bidirectional"))
    )
    (net (code "83") (name "unconnected-(U2-NC-Pad11)") (class "Default")
      (node (ref "U2") (pin "11") (pinfunction "NC_11") (pintype "bidirectional"))
    )
  )
)
